# RS485.net
KiCad netlist of a schematic drawn in Altium Designer
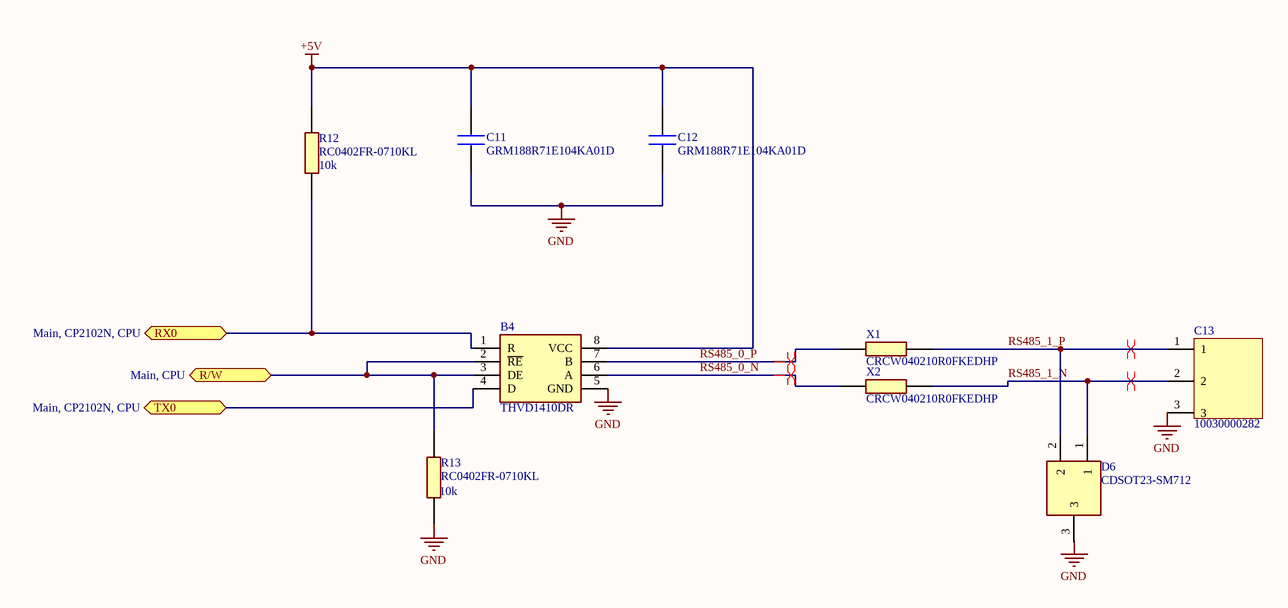
[diagram p0: RS485.SchDoc]

(export (version "E")
  (design (tool "Eeschema 10.0.6"))
  (components
    (comp (ref "B4")
      (value "THVD1410DR")
      (footprint "SOIC127P600X175-8N")
      (description "3.3-V to 5-V RS-485 transceiver with +/-18-kV IEC ESD protection")
      (fields (field (name "MOUSER PART NUMBER") "595-THVD1410DR"))
      (libsource (lib "SFMproject") (part "THVD1410DR"))
    )
    (comp (ref "C11")
      (value "GRM188R71E104KA01D")
      (footprint "CAPC1608X90N")
      (fields
        (field (name "MOUSER PART NUMBER") "81-GRM188R71E105KA2D")
        (field (name "MANUFACTURER_PART_NUMBER") "GRM188R71E105KA12D")
      )
      (libsource (lib "SFMproject") (part "GRM188R71E104KA01D"))
    )
    (comp (ref "C12")
      (value "GRM188R71E104KA01D")
      (footprint "CAPC1608X90N")
      (fields
        (field (name "MOUSER PART NUMBER") "81-GRM188R71E105KA2D")
        (field (name "MANUFACTURER_PART_NUMBER") "GRM188R71E105KA12D")
      )
      (libsource (lib "SFMproject") (part "GRM188R71E104KA01D"))
    )
    (comp (ref "C13")
      (value "10030000282")
      (footprint "15EDGRC-5.08-03P-10030000282")
      (libsource (lib "SFMproject") (part "15EDGRC-5.08-03P"))
    )
    (comp (ref "D6")
      (value "CDSOT23-SM712")
      (footprint "SOT95P237X112-3N")
      (description "Diode")
      (fields (field (name "MOUSER PART NUMBER") "652-CDSOT23-SM712"))
      (libsource (lib "SFMproject") (part "CDSOT23-SM712"))
    )
    (comp (ref "R12")
      (value "RC0402FR-0710KL")
      (footprint "RESC1005X40N")
      (description "Yageo 10k, 0402 (1005M) Thick Film SMD Resistor +/-1% 0.063W - RC0402FR-0710KL")
      (fields (field (name "MOUSER PART NUMBER") "603-RC0402FR-0710KL") (field (name "ALTIUM_VALUE") "10k"))
      (libsource (lib "SFMproject") (part "RC0402FR-0710KL"))
    )
    (comp (ref "R13")
      (value "RC0402FR-0710KL")
      (footprint "RESC1005X40N")
      (description "Yageo 10k, 0402 (1005M) Thick Film SMD Resistor +/-1% 0.063W - RC0402FR-0710KL")
      (fields (field (name "MOUSER PART NUMBER") "603-RC0402FR-0710KL") (field (name "ALTIUM_VALUE") "10k"))
      (libsource (lib "SFMproject") (part "RC0402FR-0710KL"))
    )
    (comp (ref "X1")
      (value "CRCW040210R0FKEDHP")
      (footprint "RESC1005X40N")
      (description "Résistances à couches épaisses - CMS 0.2W 10ohms 1% High Power AEC-Q200")
      (fields (field (name "MOUSER PART NUMBER") "71-CRCW040210R0FKEDH"))
      (libsource (lib "SFMproject") (part "CRCW040210R0FKEDHP"))
    )
    (comp (ref "X2")
      (value "CRCW040210R0FKEDHP")
      (footprint "RESC1005X40N")
      (description "Résistances à couches épaisses - CMS 0.2W 10ohms 1% High Power AEC-Q200")
      (fields (field (name "MOUSER PART NUMBER") "71-CRCW040210R0FKEDH"))
      (libsource (lib "SFMproject") (part "CRCW040210R0FKEDHP"))
    )
  )
  (nets
    (net (code "1") (name "+5V") (class "Default")
      (node (ref "B4") (pin "8") (pinfunction "VCC_8") (pintype "passive"))
      (node (ref "C11") (pin "2") (pinfunction "2_2") (pintype "passive"))
      (node (ref "C12") (pin "1") (pinfunction "1_1") (pintype "passive"))
      (node (ref "R12") (pin "2") (pinfunction "2_2") (pintype "passive"))
    )
    (net (code "2") (name "/RS485_0_N") (class "Default")
      (node (ref "B4") (pin "6") (pinfunction "A_6") (pintype "passive"))
      (node (ref "X2") (pin "1") (pinfunction "1_1") (pintype "passive"))
    )
    (net (code "3") (name "/RS485_0_P") (class "Default")
      (node (ref "B4") (pin "7") (pinfunction "B_7") (pintype "passive"))
      (node (ref "X1") (pin "1") (pinfunction "1_1") (pintype "passive"))
    )
    (net (code "4") (name "/RS485_1_N") (class "Default")
      (node (ref "C13") (pin "2") (pinfunction "2_2") (pintype "passive"))
      (node (ref "D6") (pin "1") (pinfunction "1_1") (pintype "passive"))
      (node (ref "X2") (pin "2") (pinfunction "2_2") (pintype "passive"))
    )
    (net (code "5") (name "/RS485_1_P") (class "Default")
      (node (ref "C13") (pin "1") (pinfunction "1_1") (pintype "passive"))
      (node (ref "D6") (pin "2") (pinfunction "2_2") (pintype "passive"))
      (node (ref "X1") (pin "2") (pinfunction "2_2") (pintype "passive"))
    )
    (net (code "6") (name "/RX0") (class "Default")
      (node (ref "B4") (pin "1") (pinfunction "R_1") (pintype "passive"))
      (node (ref "R12") (pin "1") (pinfunction "1_1") (pintype "passive"))
    )
    (net (code "7") (name "/R{slash}W") (class "Default")
      (node (ref "B4") (pin "2") (pinfunction "~{RE}_2") (pintype "passive"))
      (node (ref "B4") (pin "3") (pinfunction "DE_3") (pintype "passive"))
      (node (ref "R13") (pin "2") (pinfunction "2_2") (pintype "passive"))
    )
    (net (code "8") (name "/TX0") (class "Default")
      (node (ref "B4") (pin "4") (pinfunction "D_4") (pintype "passive"))
    )
    (net (code "9") (name "GND") (class "Default")
      (node (ref "B4") (pin "5") (pinfunction "GND_5") (pintype "passive"))
      (node (ref "C11") (pin "1") (pinfunction "1_1") (pintype "passive"))
      (node (ref "C12") (pin "2") (pinfunction "2_2") (pintype "passive"))
      (node (ref "C13") (pin "3") (pinfunction "3_3") (pintype "passive"))
      (node (ref "R13") (pin "1") (pinfunction "1_1") (pintype "passive"))
    )
    (net (code "10") (name "unconnected-(D6-Pad3)") (class "Default")
      (node (ref "D6") (pin "3") (pinfunction "3_3") (pintype "passive"))
    )
  )
)
